# MinimOSD-v11.net
KiCad netlist of a schematic drawn in EAGLE
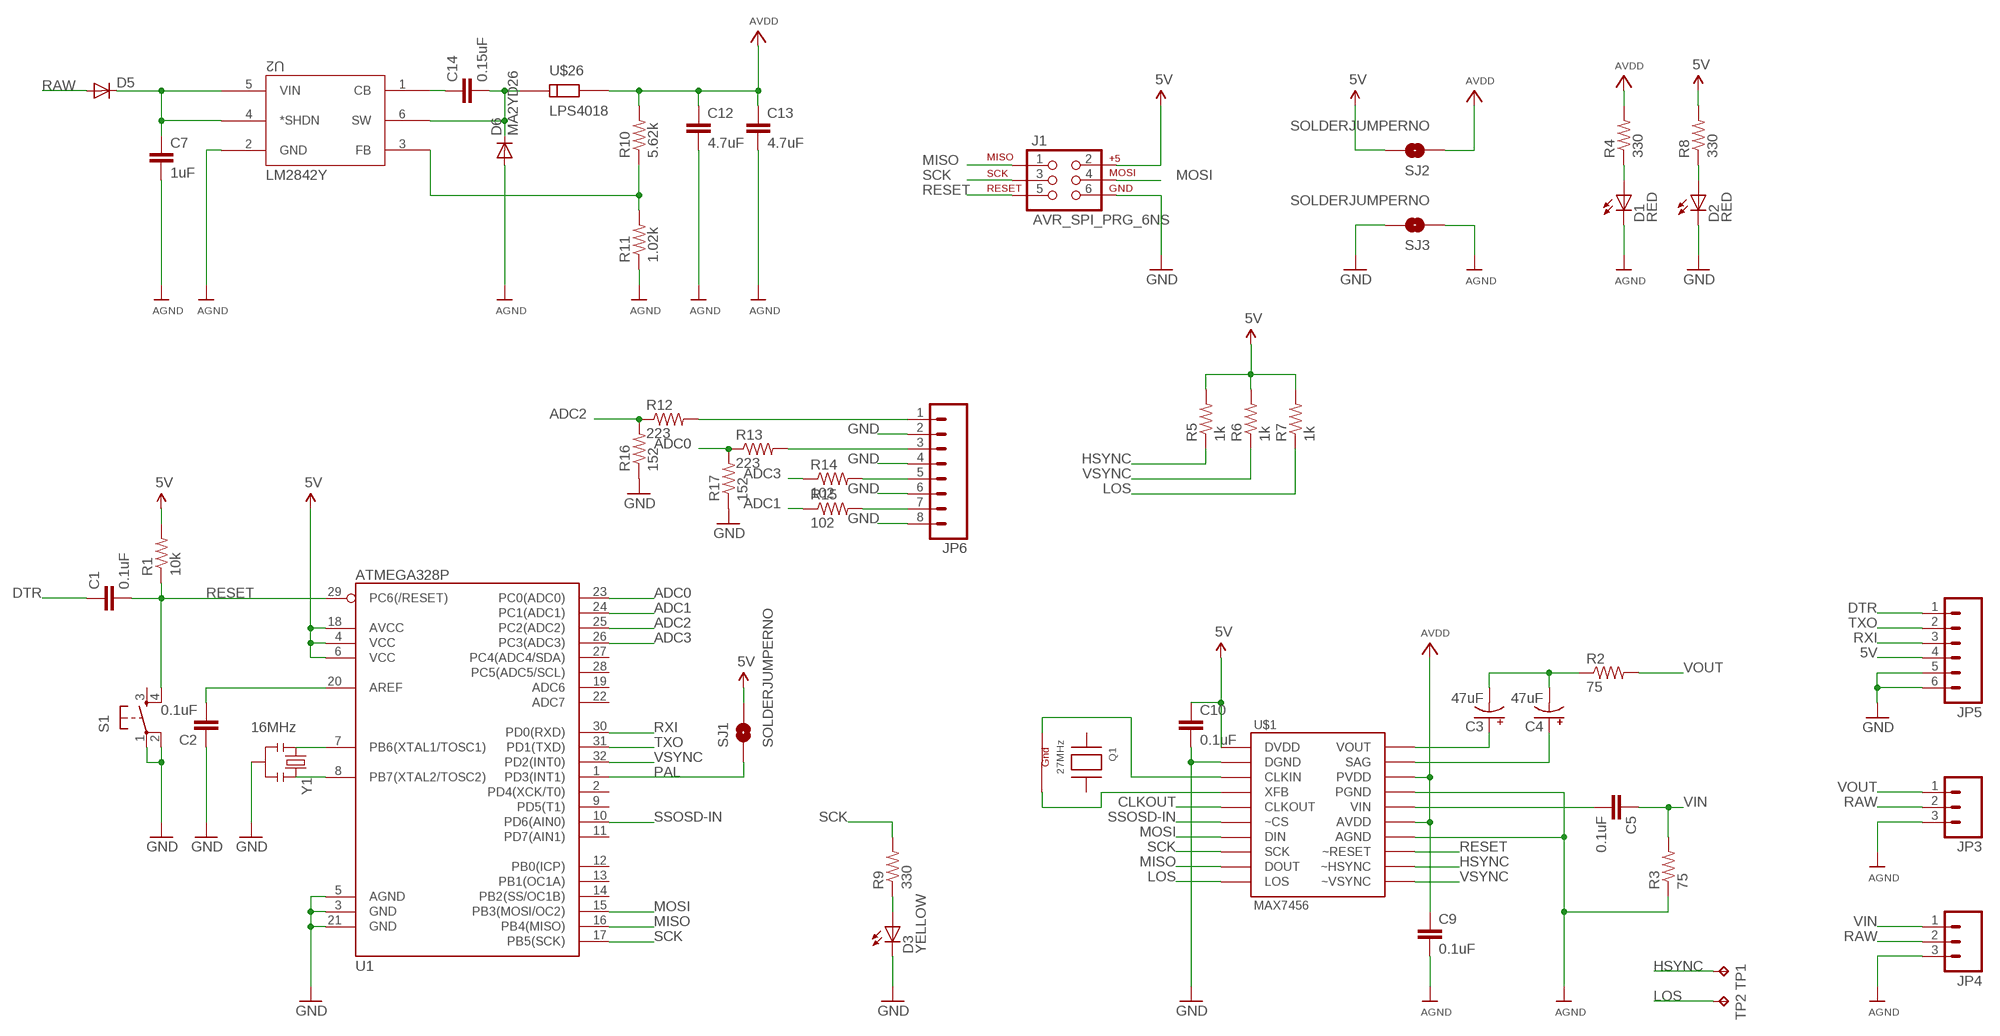
[diagram p0: schematic, sheet 1]

(export (version "E")
  (design (tool "Eeschema 10.0.6"))
  (components
    (comp (ref "C1")
      (value "0.1uF")
      (footprint "eagle-import:0402-CAP")
      (libsource (lib "eagle-import") (part "CAP0402-CAP"))
    )
    (comp (ref "C2")
      (value "0.1uF")
      (footprint "eagle-import:0402-CAP")
      (libsource (lib "eagle-import") (part "CAP0402-CAP"))
    )
    (comp (ref "C3")
      (value "47uF")
      (footprint "eagle-import:EIA3528")
      (libsource (lib "eagle-import") (part "CAP_POL3528"))
    )
    (comp (ref "C4")
      (value "47uF")
      (footprint "eagle-import:EIA3528")
      (libsource (lib "eagle-import") (part "CAP_POL3528"))
    )
    (comp (ref "C5")
      (value "0.1uF")
      (footprint "eagle-import:0402-CAP")
      (libsource (lib "eagle-import") (part "CAP0402-CAP"))
    )
    (comp (ref "C7")
      (value "1uF")
      (footprint "eagle-import:0805")
      (libsource (lib "eagle-import") (part "CAP0805"))
    )
    (comp (ref "C9")
      (value "0.1uF")
      (footprint "eagle-import:0402-CAP")
      (libsource (lib "eagle-import") (part "CAP0402-CAP"))
    )
    (comp (ref "C10")
      (value "0.1uF")
      (footprint "eagle-import:0402-CAP")
      (libsource (lib "eagle-import") (part "CAP0402-CAP"))
    )
    (comp (ref "C12")
      (value "4.7uF")
      (footprint "eagle-import:0805")
      (libsource (lib "eagle-import") (part "CAP0805"))
    )
    (comp (ref "C13")
      (value "4.7uF")
      (footprint "eagle-import:0805")
      (libsource (lib "eagle-import") (part "CAP0805"))
    )
    (comp (ref "C14")
      (value "0.15uF")
      (footprint "eagle-import:0402-CAP")
      (libsource (lib "eagle-import") (part "CAP0402-CAP"))
    )
    (comp (ref "D1")
      (value "RED")
      (footprint "eagle-import:LED-0603")
      (libsource (lib "eagle-import") (part "LED0603"))
    )
    (comp (ref "D2")
      (value "RED")
      (footprint "eagle-import:LED-0603")
      (libsource (lib "eagle-import") (part "LED0603"))
    )
    (comp (ref "D3")
      (value "YELLOW")
      (footprint "eagle-import:LED-0603")
      (libsource (lib "eagle-import") (part "LED0603"))
    )
    (comp (ref "D5")
      (value "DIODE-SOD123")
      (footprint "eagle-import:SOD123")
      (libsource (lib "eagle-import") (part "DIODE-SOD123"))
    )
    (comp (ref "D6")
      (value "MA2YD26")
      (footprint "eagle-import:SOD123")
      (libsource (lib "eagle-import") (part "DIODE-SOD123"))
    )
    (comp (ref "J1")
      (value "AVR_SPI_PRG_6NS")
      (footprint "eagle-import:2X3-NS")
      (libsource (lib "eagle-import") (part "AVR_SPI_PRG_6NS"))
    )
    (comp (ref "JP3")
      (value "M03PTH")
      (footprint "eagle-import:1X03")
      (libsource (lib "eagle-import") (part "M03PTH"))
    )
    (comp (ref "JP4")
      (value "M03PTH")
      (footprint "eagle-import:1X03")
      (libsource (lib "eagle-import") (part "M03PTH"))
    )
    (comp (ref "JP5")
      (value "M06SIP")
      (footprint "eagle-import:1X06")
      (libsource (lib "eagle-import") (part "M06SIP"))
    )
    (comp (ref "JP6")
      (value "M081X08")
      (footprint "eagle-import:1X08")
      (libsource (lib "eagle-import") (part "M081X08"))
    )
    (comp (ref "Q1")
      (value "27MHz")
      (footprint "eagle-import:NX3225")
      (libsource (lib "eagle-import") (part "XTAL-4-3225"))
    )
    (comp (ref "R1")
      (value "10k")
      (footprint "eagle-import:0402-RES")
      (libsource (lib "eagle-import") (part "RESISTOR0402-RES"))
    )
    (comp (ref "R2")
      (value "75")
      (footprint "eagle-import:0402-RES")
      (libsource (lib "eagle-import") (part "RESISTOR0402-RES"))
    )
    (comp (ref "R3")
      (value "75")
      (footprint "eagle-import:0402-RES")
      (libsource (lib "eagle-import") (part "RESISTOR0402-RES"))
    )
    (comp (ref "R4")
      (value "330")
      (footprint "eagle-import:0402-RES")
      (libsource (lib "eagle-import") (part "RESISTOR0402-RES"))
    )
    (comp (ref "R5")
      (value "1k")
      (footprint "eagle-import:0402-RES")
      (libsource (lib "eagle-import") (part "RESISTOR0402-RES"))
    )
    (comp (ref "R6")
      (value "1k")
      (footprint "eagle-import:0402-RES")
      (libsource (lib "eagle-import") (part "RESISTOR0402-RES"))
    )
    (comp (ref "R7")
      (value "1k")
      (footprint "eagle-import:0402-RES")
      (libsource (lib "eagle-import") (part "RESISTOR0402-RES"))
    )
    (comp (ref "R8")
      (value "330")
      (footprint "eagle-import:0402-RES")
      (libsource (lib "eagle-import") (part "RESISTOR0402-RES"))
    )
    (comp (ref "R9")
      (value "330")
      (footprint "eagle-import:0402-RES")
      (libsource (lib "eagle-import") (part "RESISTOR0402-RES"))
    )
    (comp (ref "R10")
      (value "5.62k")
      (footprint "eagle-import:0402-RES")
      (libsource (lib "eagle-import") (part "RESISTOR0402-RES"))
    )
    (comp (ref "R11")
      (value "1.02k")
      (footprint "eagle-import:0402-RES")
      (libsource (lib "eagle-import") (part "RESISTOR0402-RES"))
    )
    (comp (ref "R12")
      (value "223")
      (footprint "eagle-import:0402-RES")
      (libsource (lib "eagle-import") (part "SparkFun-Passives_RESISTOR0402-RES"))
    )
    (comp (ref "R13")
      (value "223")
      (footprint "eagle-import:0402-RES")
      (libsource (lib "eagle-import") (part "SparkFun-Passives_RESISTOR0402-RES"))
    )
    (comp (ref "R14")
      (value "102")
      (footprint "eagle-import:0402-RES")
      (libsource (lib "eagle-import") (part "SparkFun-Passives_RESISTOR0402-RES"))
    )
    (comp (ref "R15")
      (value "102")
      (footprint "eagle-import:0402-RES")
      (libsource (lib "eagle-import") (part "SparkFun-Passives_RESISTOR0402-RES"))
    )
    (comp (ref "R16")
      (value "152")
      (footprint "eagle-import:0402-RES")
      (libsource (lib "eagle-import") (part "SparkFun-Passives_RESISTOR0402-RES"))
    )
    (comp (ref "R17")
      (value "152")
      (footprint "eagle-import:0402-RES")
      (libsource (lib "eagle-import") (part "SparkFun-Passives_RESISTOR0402-RES"))
    )
    (comp (ref "S1")
      (value "TAC_SWITCHSMD")
      (footprint "eagle-import:TACTILE_SWITCH_SMD")
      (libsource (lib "eagle-import") (part "TAC_SWITCHSMD"))
    )
    (comp (ref "SJ1")
      (value "SOLDERJUMPERNO")
      (footprint "eagle-import:SJ_2S-NO")
      (libsource (lib "eagle-import") (part "SOLDERJUMPERNO"))
    )
    (comp (ref "SJ2")
      (value "SOLDERJUMPERNO")
      (footprint "eagle-import:SJ_2S-NO")
      (libsource (lib "eagle-import") (part "SOLDERJUMPERNO"))
    )
    (comp (ref "SJ3")
      (value "SOLDERJUMPERNO")
      (footprint "eagle-import:SJ_2S-NO")
      (libsource (lib "eagle-import") (part "SOLDERJUMPERNO"))
    )
    (comp (ref "TP1")
      (value "TPTP12SQ")
      (footprint "eagle-import:TP12SQ")
      (libsource (lib "eagle-import") (part "TPTP12SQ"))
    )
    (comp (ref "TP2")
      (value "TPTP12SQ")
      (footprint "eagle-import:TP12SQ")
      (libsource (lib "eagle-import") (part "TPTP12SQ"))
    )
    (comp (ref "U$1")
      (value "MAX7456")
      (footprint "eagle-import:TSSOP28")
      (libsource (lib "eagle-import") (part "MAX7456"))
    )
    (comp (ref "U$26")
      (value "LPS4018")
      (footprint "eagle-import:LPS4018")
      (libsource (lib "eagle-import") (part "LPS4018"))
    )
    (comp (ref "U1")
      (value "ATMEGA328P")
      (footprint "eagle-import:TQFP32-08")
      (libsource (lib "eagle-import") (part "ATMEGA168"))
    )
    (comp (ref "U2")
      (value "LM2842Y")
      (footprint "eagle-import:MK06A")
      (libsource (lib "eagle-import") (part "LM2842"))
    )
    (comp (ref "Y1")
      (value "16MHz")
      (footprint "eagle-import:RESONATOR-SMD")
      (libsource (lib "eagle-import") (part "RESONATORSMD"))
    )
  )
  (nets
    (net (code "1") (name "/ADC0") (class "Default")
      (node (ref "R13") (pin "1") (pinfunction "1_1") (pintype "passive"))
      (node (ref "R17") (pin "2") (pinfunction "2_2") (pintype "passive"))
      (node (ref "U1") (pin "23") (pinfunction "PC0(ADC0)_23") (pintype "bidirectional"))
    )
    (net (code "2") (name "/ADC1") (class "Default")
      (node (ref "R15") (pin "1") (pinfunction "1_1") (pintype "passive"))
      (node (ref "U1") (pin "24") (pinfunction "PC1(ADC1)_24") (pintype "bidirectional"))
    )
    (net (code "3") (name "/ADC2") (class "Default")
      (node (ref "R12") (pin "1") (pinfunction "1_1") (pintype "passive"))
      (node (ref "R16") (pin "2") (pinfunction "2_2") (pintype "passive"))
      (node (ref "U1") (pin "25") (pinfunction "PC2(ADC2)_25") (pintype "bidirectional"))
    )
    (net (code "4") (name "/ADC3") (class "Default")
      (node (ref "R14") (pin "1") (pinfunction "1_1") (pintype "passive"))
      (node (ref "U1") (pin "26") (pinfunction "PC3(ADC3)_26") (pintype "bidirectional"))
    )
    (net (code "5") (name "/CLKOUT") (class "Default")
      (node (ref "U$1") (pin "7") (pinfunction "CLKOUT_7") (pintype "bidirectional"))
    )
    (net (code "6") (name "/DTR") (class "Default")
      (node (ref "C1") (pin "1") (pinfunction "1_1") (pintype "passive"))
      (node (ref "JP5") (pin "1") (pinfunction "1_1") (pintype "passive"))
    )
    (net (code "7") (name "/HSYNC") (class "Default")
      (node (ref "R5") (pin "1") (pinfunction "1_1") (pintype "passive"))
      (node (ref "TP1") (pin "TP") (pinfunction "TP_TP") (pintype "input"))
      (node (ref "U$1") (pin "18") (pinfunction "~{HSYNC}_18") (pintype "bidirectional"))
    )
    (net (code "8") (name "/LOS") (class "Default")
      (node (ref "R7") (pin "1") (pinfunction "1_1") (pintype "passive"))
      (node (ref "TP2") (pin "TP") (pinfunction "TP_TP") (pintype "input"))
      (node (ref "U$1") (pin "12") (pinfunction "LOS_12") (pintype "bidirectional"))
    )
    (net (code "9") (name "/MISO") (class "Default")
      (node (ref "J1") (pin "1") (pinfunction "1_1") (pintype "passive"))
      (node (ref "U$1") (pin "11") (pinfunction "DOUT_11") (pintype "bidirectional"))
      (node (ref "U1") (pin "16") (pinfunction "PB4(MISO)_16") (pintype "bidirectional"))
    )
    (net (code "10") (name "/MOSI") (class "Default")
      (node (ref "J1") (pin "4") (pinfunction "4_4") (pintype "passive"))
      (node (ref "U$1") (pin "9") (pinfunction "DIN_9") (pintype "bidirectional"))
      (node (ref "U1") (pin "15") (pinfunction "PB3(MOSI/OC2)_15") (pintype "bidirectional"))
    )
    (net (code "11") (name "/PAL") (class "Default")
      (node (ref "SJ1") (pin "1") (pinfunction "1_1") (pintype "passive"))
      (node (ref "U1") (pin "1") (pinfunction "PD3(INT1)_1") (pintype "bidirectional"))
    )
    (net (code "12") (name "/RAW") (class "Default")
      (node (ref "D5") (pin "A") (pinfunction "A_A") (pintype "passive"))
      (node (ref "JP3") (pin "2") (pinfunction "2_2") (pintype "passive"))
      (node (ref "JP4") (pin "2") (pinfunction "2_2") (pintype "passive"))
    )
    (net (code "13") (name "/RESET") (class "Default")
      (node (ref "C1") (pin "2") (pinfunction "2_2") (pintype "passive"))
      (node (ref "J1") (pin "5") (pinfunction "5_5") (pintype "passive"))
      (node (ref "R1") (pin "1") (pinfunction "1_1") (pintype "passive"))
      (node (ref "S1") (pin "4") (pinfunction "4_4") (pintype "passive"))
      (node (ref "U$1") (pin "19") (pinfunction "~{RESET}_19") (pintype "bidirectional"))
      (node (ref "U1") (pin "29") (pinfunction "PC6(/RESET)_29") (pintype "bidirectional"))
    )
    (net (code "14") (name "/RXI") (class "Default")
      (node (ref "JP5") (pin "3") (pinfunction "3_3") (pintype "passive"))
      (node (ref "U1") (pin "30") (pinfunction "PD0(RXD)_30") (pintype "bidirectional"))
    )
    (net (code "15") (name "/SCK") (class "Default")
      (node (ref "J1") (pin "3") (pinfunction "3_3") (pintype "passive"))
      (node (ref "R9") (pin "2") (pinfunction "2_2") (pintype "passive"))
      (node (ref "U$1") (pin "10") (pinfunction "SCK_10") (pintype "bidirectional"))
      (node (ref "U1") (pin "17") (pinfunction "PB5(SCK)_17") (pintype "bidirectional"))
    )
    (net (code "16") (name "/SSOSD-IN") (class "Default")
      (node (ref "U$1") (pin "8") (pinfunction "~{CS}_8") (pintype "bidirectional"))
      (node (ref "U1") (pin "10") (pinfunction "PD6(AIN0)_10") (pintype "bidirectional"))
    )
    (net (code "17") (name "/TXO") (class "Default")
      (node (ref "JP5") (pin "2") (pinfunction "2_2") (pintype "passive"))
      (node (ref "U1") (pin "31") (pinfunction "PD1(TXD)_31") (pintype "bidirectional"))
    )
    (net (code "18") (name "/VIN") (class "Default")
      (node (ref "C5") (pin "1") (pinfunction "1_1") (pintype "passive"))
      (node (ref "JP4") (pin "1") (pinfunction "1_1") (pintype "passive"))
      (node (ref "R3") (pin "2") (pinfunction "2_2") (pintype "passive"))
    )
    (net (code "19") (name "/VOUT") (class "Default")
      (node (ref "JP3") (pin "1") (pinfunction "1_1") (pintype "passive"))
      (node (ref "R2") (pin "2") (pinfunction "2_2") (pintype "passive"))
    )
    (net (code "20") (name "/VSYNC") (class "Default")
      (node (ref "R6") (pin "1") (pinfunction "1_1") (pintype "passive"))
      (node (ref "U$1") (pin "17") (pinfunction "~{VSYNC}_17") (pintype "bidirectional"))
      (node (ref "U1") (pin "32") (pinfunction "PD2(INT0)_32") (pintype "bidirectional"))
    )
    (net (code "21") (name "5V") (class "Default")
      (node (ref "C10") (pin "1") (pinfunction "1_1") (pintype "passive"))
      (node (ref "J1") (pin "2") (pinfunction "2_2") (pintype "passive"))
      (node (ref "JP5") (pin "4") (pinfunction "4_4") (pintype "passive"))
      (node (ref "R1") (pin "2") (pinfunction "2_2") (pintype "passive"))
      (node (ref "R5") (pin "2") (pinfunction "2_2") (pintype "passive"))
      (node (ref "R6") (pin "2") (pinfunction "2_2") (pintype "passive"))
      (node (ref "R7") (pin "2") (pinfunction "2_2") (pintype "passive"))
      (node (ref "R8") (pin "2") (pinfunction "2_2") (pintype "passive"))
      (node (ref "SJ1") (pin "2") (pinfunction "2_2") (pintype "passive"))
      (node (ref "SJ2") (pin "2") (pinfunction "2_2") (pintype "passive"))
      (node (ref "U$1") (pin "3") (pinfunction "DVDD_3") (pintype "bidirectional"))
      (node (ref "U1") (pin "18") (pinfunction "AVCC_18") (pintype "bidirectional"))
      (node (ref "U1") (pin "4") (pinfunction "VCC_4") (pintype "bidirectional"))
      (node (ref "U1") (pin "6") (pinfunction "VCC_6") (pintype "bidirectional"))
    )
    (net (code "22") (name "AGND") (class "Default")
      (node (ref "C12") (pin "2") (pinfunction "2_2") (pintype "passive"))
      (node (ref "C13") (pin "2") (pinfunction "2_2") (pintype "passive"))
      (node (ref "C7") (pin "2") (pinfunction "2_2") (pintype "passive"))
      (node (ref "C9") (pin "2") (pinfunction "2_2") (pintype "passive"))
      (node (ref "D1") (pin "C") (pinfunction "C_C") (pintype "passive"))
      (node (ref "D6") (pin "A") (pinfunction "A_A") (pintype "passive"))
      (node (ref "JP3") (pin "3") (pinfunction "3_3") (pintype "passive"))
      (node (ref "JP4") (pin "3") (pinfunction "3_3") (pintype "passive"))
      (node (ref "R11") (pin "1") (pinfunction "1_1") (pintype "passive"))
      (node (ref "R3") (pin "1") (pinfunction "1_1") (pintype "passive"))
      (node (ref "SJ3") (pin "1") (pinfunction "1_1") (pintype "passive"))
      (node (ref "U$1") (pin "20") (pinfunction "AGND_20") (pintype "bidirectional"))
      (node (ref "U$1") (pin "23") (pinfunction "PGND_23") (pintype "bidirectional"))
      (node (ref "U2") (pin "2") (pinfunction "GND_2") (pintype "passive"))
    )
    (net (code "23") (name "AVDD") (class "Default")
      (node (ref "C12") (pin "1") (pinfunction "1_1") (pintype "passive"))
      (node (ref "C13") (pin "1") (pinfunction "1_1") (pintype "passive"))
      (node (ref "C9") (pin "1") (pinfunction "1_1") (pintype "passive"))
      (node (ref "R10") (pin "2") (pinfunction "2_2") (pintype "passive"))
      (node (ref "R4") (pin "2") (pinfunction "2_2") (pintype "passive"))
      (node (ref "SJ2") (pin "1") (pinfunction "1_1") (pintype "passive"))
      (node (ref "U$1") (pin "21") (pinfunction "AVDD_21") (pintype "bidirectional"))
      (node (ref "U$1") (pin "24") (pinfunction "PVDD_24") (pintype "bidirectional"))
      (node (ref "U$26") (pin "B") (pinfunction "B_B") (pintype "bidirectional"))
    )
    (net (code "24") (name "GND") (class "Default")
      (node (ref "C10") (pin "2") (pinfunction "2_2") (pintype "passive"))
      (node (ref "C2") (pin "1") (pinfunction "1_1") (pintype "passive"))
      (node (ref "D2") (pin "C") (pinfunction "C_C") (pintype "passive"))
      (node (ref "D3") (pin "C") (pinfunction "C_C") (pintype "passive"))
      (node (ref "J1") (pin "6") (pinfunction "6_6") (pintype "passive"))
      (node (ref "JP5") (pin "5") (pinfunction "5_5") (pintype "passive"))
      (node (ref "JP5") (pin "6") (pinfunction "6_6") (pintype "passive"))
      (node (ref "JP6") (pin "2") (pinfunction "2_2") (pintype "passive"))
      (node (ref "JP6") (pin "4") (pinfunction "4_4") (pintype "passive"))
      (node (ref "JP6") (pin "6") (pinfunction "6_6") (pintype "passive"))
      (node (ref "JP6") (pin "8") (pinfunction "8_8") (pintype "passive"))
      (node (ref "R16") (pin "1") (pinfunction "1_1") (pintype "passive"))
      (node (ref "R17") (pin "1") (pinfunction "1_1") (pintype "passive"))
      (node (ref "S1") (pin "1") (pinfunction "1_1") (pintype "passive"))
      (node (ref "S1") (pin "2") (pinfunction "2_2") (pintype "passive"))
      (node (ref "SJ3") (pin "2") (pinfunction "2_2") (pintype "passive"))
      (node (ref "U$1") (pin "4") (pinfunction "DGND_4") (pintype "bidirectional"))
      (node (ref "U1") (pin "21") (pinfunction "GND_21") (pintype "bidirectional"))
      (node (ref "U1") (pin "3") (pinfunction "GND_3") (pintype "bidirectional"))
      (node (ref "U1") (pin "5") (pinfunction "AGND_5") (pintype "bidirectional"))
      (node (ref "Y1") (pin "2") (pinfunction "2_2") (pintype "passive"))
    )
    (net (code "25") (name "Net-(C3-+)") (class "Default")
      (node (ref "C3") (pin "A") (pinfunction "+_A") (pintype "passive"))
      (node (ref "U$1") (pin "26") (pinfunction "VOUT_26") (pintype "bidirectional"))
    )
    (net (code "26") (name "Net-(C3--)") (class "Default")
      (node (ref "C3") (pin "C") (pinfunction "-_C") (pintype "passive"))
      (node (ref "C4") (pin "C") (pinfunction "-_C") (pintype "passive"))
      (node (ref "R2") (pin "1") (pinfunction "1_1") (pintype "passive"))
    )
    (net (code "27") (name "Net-(C4-+)") (class "Default")
      (node (ref "C4") (pin "A") (pinfunction "+_A") (pintype "passive"))
      (node (ref "U$1") (pin "25") (pinfunction "SAG_25") (pintype "bidirectional"))
    )
    (net (code "28") (name "Net-(D1-PadA)") (class "Default")
      (node (ref "D1") (pin "A") (pinfunction "A_A") (pintype "passive"))
      (node (ref "R4") (pin "1") (pinfunction "1_1") (pintype "passive"))
    )
    (net (code "29") (name "Net-(D2-PadA)") (class "Default")
      (node (ref "D2") (pin "A") (pinfunction "A_A") (pintype "passive"))
      (node (ref "R8") (pin "1") (pinfunction "1_1") (pintype "passive"))
    )
    (net (code "30") (name "Net-(D3-PadA)") (class "Default")
      (node (ref "D3") (pin "A") (pinfunction "A_A") (pintype "passive"))
      (node (ref "R9") (pin "1") (pinfunction "1_1") (pintype "passive"))
    )
    (net (code "31") (name "Net-(JP6-Pad1)") (class "Default")
      (node (ref "JP6") (pin "1") (pinfunction "1_1") (pintype "passive"))
      (node (ref "R12") (pin "2") (pinfunction "2_2") (pintype "passive"))
    )
    (net (code "32") (name "Net-(JP6-Pad3)") (class "Default")
      (node (ref "JP6") (pin "3") (pinfunction "3_3") (pintype "passive"))
      (node (ref "R13") (pin "2") (pinfunction "2_2") (pintype "passive"))
    )
    (net (code "33") (name "Net-(JP6-Pad5)") (class "Default")
      (node (ref "JP6") (pin "5") (pinfunction "5_5") (pintype "passive"))
      (node (ref "R14") (pin "2") (pinfunction "2_2") (pintype "passive"))
    )
    (net (code "34") (name "Net-(JP6-Pad7)") (class "Default")
      (node (ref "JP6") (pin "7") (pinfunction "7_7") (pintype "passive"))
      (node (ref "R15") (pin "2") (pinfunction "2_2") (pintype "passive"))
    )
    (net (code "35") (name "Net-(Q1-G1)") (class "Default")
      (node (ref "Q1") (pin "2") (pinfunction "G1_2") (pintype "power_in"))
      (node (ref "U$1") (pin "5") (pinfunction "CLKIN_5") (pintype "bidirectional"))
    )
    (net (code "36") (name "Net-(Q1-G2)") (class "Default")
      (node (ref "Q1") (pin "4") (pinfunction "G2_4") (pintype "power_in"))
      (node (ref "U$1") (pin "6") (pinfunction "XFB_6") (pintype "bidirectional"))
    )
    (net (code "37") (name "Net-(U$1-VIN)") (class "Default")
      (node (ref "C5") (pin "2") (pinfunction "2_2") (pintype "passive"))
      (node (ref "U$1") (pin "22") (pinfunction "VIN_22") (pintype "bidirectional"))
    )
    (net (code "38") (name "Net-(U1-AREF)") (class "Default")
      (node (ref "C2") (pin "2") (pinfunction "2_2") (pintype "passive"))
      (node (ref "U1") (pin "20") (pinfunction "AREF_20") (pintype "bidirectional"))
    )
    (net (code "39") (name "Net-(U1-PB6(XTAL1{slash}TOSC1))") (class "Default")
      (node (ref "U1") (pin "7") (pinfunction "PB6(XTAL1/TOSC1)_7") (pintype "bidirectional"))
      (node (ref "Y1") (pin "1") (pinfunction "1_1") (pintype "passive"))
    )
    (net (code "40") (name "Net-(U1-PB7(XTAL2{slash}TOSC2))") (class "Default")
      (node (ref "U1") (pin "8") (pinfunction "PB7(XTAL2/TOSC2)_8") (pintype "bidirectional"))
      (node (ref "Y1") (pin "3") (pinfunction "3_3") (pintype "passive"))
    )
    (net (code "41") (name "Net-(U2-*SHDN)") (class "Default")
      (node (ref "C7") (pin "1") (pinfunction "1_1") (pintype "passive"))
      (node (ref "D5") (pin "C") (pinfunction "C_C") (pintype "passive"))
      (node (ref "U2") (pin "4") (pinfunction "*SHDN_4") (pintype "passive"))
      (node (ref "U2") (pin "5") (pinfunction "VIN_5") (pintype "passive"))
    )
    (net (code "42") (name "Net-(U2-CB)") (class "Default")
      (node (ref "C14") (pin "1") (pinfunction "1_1") (pintype "passive"))
      (node (ref "U2") (pin "1") (pinfunction "CB_1") (pintype "passive"))
    )
    (net (code "43") (name "Net-(U2-FB)") (class "Default")
      (node (ref "R10") (pin "1") (pinfunction "1_1") (pintype "passive"))
      (node (ref "R11") (pin "2") (pinfunction "2_2") (pintype "passive"))
      (node (ref "U2") (pin "3") (pinfunction "FB_3") (pintype "passive"))
    )
    (net (code "44") (name "Net-(U2-SW)") (class "Default")
      (node (ref "C14") (pin "2") (pinfunction "2_2") (pintype "passive"))
      (node (ref "D6") (pin "C") (pinfunction "C_C") (pintype "passive"))
      (node (ref "U$26") (pin "A") (pinfunction "A_A") (pintype "bidirectional"))
      (node (ref "U2") (pin "6") (pinfunction "SW_6") (pintype "passive"))
    )
    (net (code "45") (name "unconnected-(Q1-X1-Pad1)") (class "Default")
      (node (ref "Q1") (pin "1") (pinfunction "X1_1") (pintype "bidirectional"))
    )
    (net (code "46") (name "unconnected-(Q1-X2-Pad3)") (class "Default")
      (node (ref "Q1") (pin "3") (pinfunction "X2_3") (pintype "bidirectional"))
    )
    (net (code "47") (name "unconnected-(S1-Pad3)") (class "Default")
      (node (ref "S1") (pin "3") (pinfunction "3_3") (pintype "passive"))
    )
    (net (code "48") (name "unconnected-(U1-ADC6-Pad19)") (class "Default")
      (node (ref "U1") (pin "19") (pinfunction "ADC6_19") (pintype "bidirectional"))
    )
    (net (code "49") (name "unconnected-(U1-ADC7-Pad22)") (class "Default")
      (node (ref "U1") (pin "22") (pinfunction "ADC7_22") (pintype "bidirectional"))
    )
    (net (code "50") (name "unconnected-(U1-PB0(ICP)-Pad12)") (class "Default")
      (node (ref "U1") (pin "12") (pinfunction "PB0(ICP)_12") (pintype "bidirectional"))
    )
    (net (code "51") (name "unconnected-(U1-PB1(OC1A)-Pad13)") (class "Default")
      (node (ref "U1") (pin "13") (pinfunction "PB1(OC1A)_13") (pintype "bidirectional"))
    )
    (net (code "52") (name "unconnected-(U1-PB2(SS{slash}OC1B)-Pad14)") (class "Default")
      (node (ref "U1") (pin "14") (pinfunction "PB2(SS/OC1B)_14") (pintype "bidirectional"))
    )
    (net (code "53") (name "unconnected-(U1-PC4(ADC4{slash}SDA)-Pad27)") (class "Default")
      (node (ref "U1") (pin "27") (pinfunction "PC4(ADC4/SDA)_27") (pintype "bidirectional"))
    )
    (net (code "54") (name "unconnected-(U1-PC5(ADC5{slash}SCL)-Pad28)") (class "Default")
      (node (ref "U1") (pin "28") (pinfunction "PC5(ADC5/SCL)_28") (pintype "bidirectional"))
    )
    (net (code "55") (name "unconnected-(U1-PD4(XCK{slash}T0)-Pad2)") (class "Default")
      (node (ref "U1") (pin "2") (pinfunction "PD4(XCK/T0)_2") (pintype "bidirectional"))
    )
    (net (code "56") (name "unconnected-(U1-PD5(T1)-Pad9)") (class "Default")
      (node (ref "U1") (pin "9") (pinfunction "PD5(T1)_9") (pintype "bidirectional"))
    )
    (net (code "57") (name "unconnected-(U1-PD7(AIN1)-Pad11)") (class "Default")
      (node (ref "U1") (pin "11") (pinfunction "PD7(AIN1)_11") (pintype "bidirectional"))
    )
  )
)
